# Transceivers_Ver2.net
KiCad netlist of a schematic drawn in EAGLE
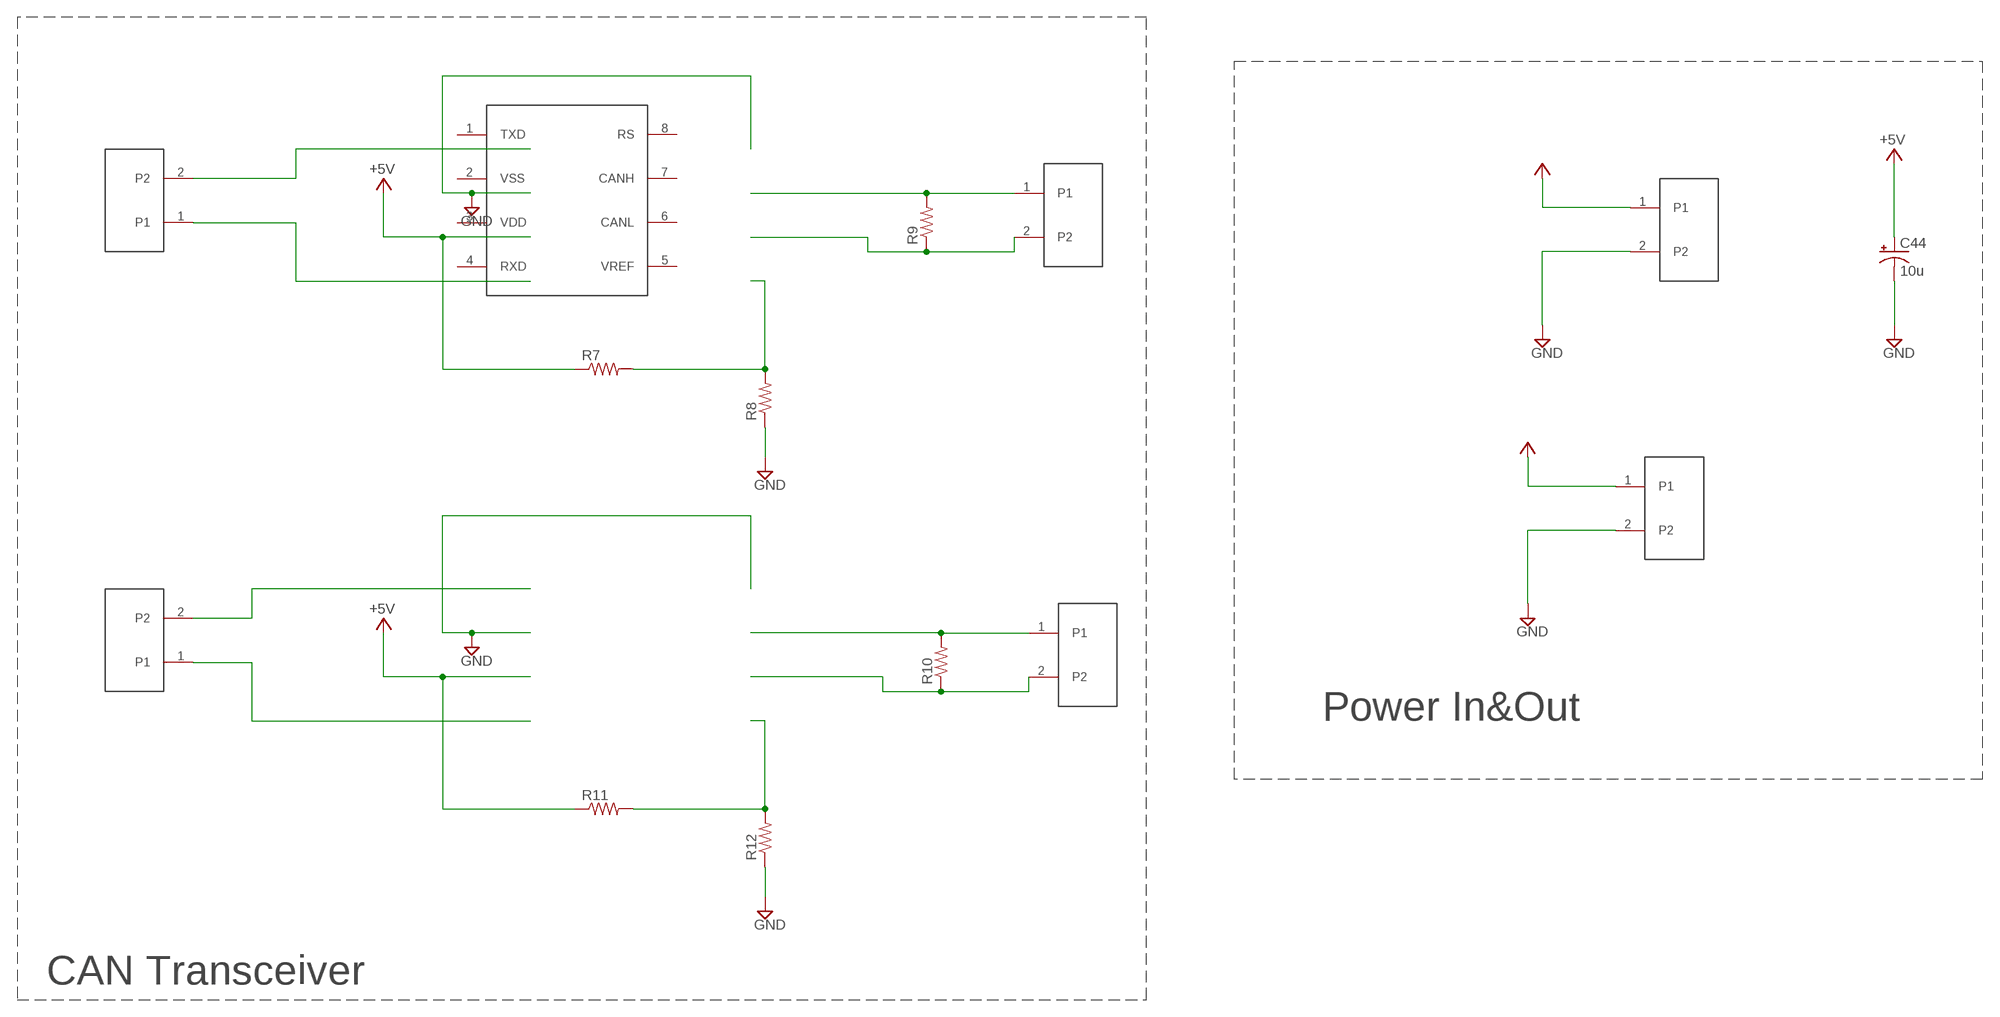
[diagram p0: schematic, sheet 1]

(export (version "E")
  (design (tool "Eeschema 10.0.6"))
  (components
    (comp (ref "C44")
      (value "10u")
      (footprint "eagle-import:153CLV-0405")
      (libsource (lib "eagle-import") (part "CPOL-US153CLV-0405"))
    )
    (comp (ref "CAN0")
      (value "CON-100MIL")
      (footprint "eagle-import:2X1-100MIL")
      (libsource (lib "eagle-import") (part "CON-100MIL"))
    )
    (comp (ref "CAN1")
      (value "CON-100MIL")
      (footprint "eagle-import:2X1-100MIL")
      (libsource (lib "eagle-import") (part "CON-100MIL"))
    )
    (comp (ref "POWER")
      (value "CON-100MIL")
      (footprint "eagle-import:2X1-100MIL")
      (libsource (lib "eagle-import") (part "CON-100MIL"))
    )
    (comp (ref "POWER1")
      (value "CON-100MIL")
      (footprint "eagle-import:2X1-100MIL")
      (libsource (lib "eagle-import") (part "CON-100MIL"))
    )
    (comp (ref "R7")
      (value "R-US_R0805")
      (footprint "eagle-import:R0805")
      (libsource (lib "eagle-import") (part "R-US_R0805"))
    )
    (comp (ref "R8")
      (value "R-US_R0805")
      (footprint "eagle-import:R0805")
      (libsource (lib "eagle-import") (part "R-US_R0805"))
    )
    (comp (ref "R9")
      (value "R-US_R0805")
      (footprint "eagle-import:R0805")
      (libsource (lib "eagle-import") (part "R-US_R0805"))
    )
    (comp (ref "R10")
      (value "R-US_R0805")
      (footprint "eagle-import:R0805")
      (libsource (lib "eagle-import") (part "R-US_R0805"))
    )
    (comp (ref "R11")
      (value "R-US_R0805")
      (footprint "eagle-import:R0805")
      (libsource (lib "eagle-import") (part "R-US_R0805"))
    )
    (comp (ref "R12")
      (value "R-US_R0805")
      (footprint "eagle-import:R0805")
      (libsource (lib "eagle-import") (part "R-US_R0805"))
    )
    (comp (ref "TXRX0")
      (value "CON-100MIL")
      (footprint "eagle-import:2X1-100MIL")
      (libsource (lib "eagle-import") (part "CON-100MIL"))
    )
    (comp (ref "TXRX1")
      (value "CON-100MIL")
      (footprint "eagle-import:2X1-100MIL")
      (libsource (lib "eagle-import") (part "CON-100MIL"))
    )
    (comp (ref "U$1")
      (value "MCP2551-DIP")
      (footprint "eagle-import:DIL08")
      (libsource (lib "eagle-import") (part "MCP2551-DIP"))
    )
  )
  (nets
    (net (code "1") (name "+5V") (class "Default")
      (node (ref "C44") (pin "+") (pinfunction "+_+") (pintype "passive"))
      (node (ref "POWER") (pin "1") (pinfunction "P1_1") (pintype "bidirectional"))
      (node (ref "POWER1") (pin "1") (pinfunction "P1_1") (pintype "bidirectional"))
      (node (ref "R11") (pin "1") (pinfunction "1_1") (pintype "passive"))
      (node (ref "R7") (pin "1") (pinfunction "1_1") (pintype "passive"))
    )
    (net (code "2") (name "GND") (class "Default")
      (node (ref "C44") (pin "-") (pinfunction "-_-") (pintype "passive"))
      (node (ref "POWER") (pin "2") (pinfunction "P2_2") (pintype "bidirectional"))
      (node (ref "POWER1") (pin "2") (pinfunction "P2_2") (pintype "bidirectional"))
      (node (ref "R12") (pin "1") (pinfunction "1_1") (pintype "passive"))
      (node (ref "R8") (pin "1") (pinfunction "1_1") (pintype "passive"))
    )
    (net (code "3") (name "Net-(CAN0-P1)") (class "Default")
      (node (ref "CAN0") (pin "1") (pinfunction "P1_1") (pintype "bidirectional"))
      (node (ref "R9") (pin "2") (pinfunction "2_2") (pintype "passive"))
    )
    (net (code "4") (name "Net-(CAN0-P2)") (class "Default")
      (node (ref "CAN0") (pin "2") (pinfunction "P2_2") (pintype "bidirectional"))
      (node (ref "R9") (pin "1") (pinfunction "1_1") (pintype "passive"))
    )
    (net (code "5") (name "Net-(CAN1-P1)") (class "Default")
      (node (ref "CAN1") (pin "1") (pinfunction "P1_1") (pintype "bidirectional"))
      (node (ref "R10") (pin "2") (pinfunction "2_2") (pintype "passive"))
    )
    (net (code "6") (name "Net-(CAN1-P2)") (class "Default")
      (node (ref "CAN1") (pin "2") (pinfunction "P2_2") (pintype "bidirectional"))
      (node (ref "R10") (pin "1") (pinfunction "1_1") (pintype "passive"))
    )
    (net (code "7") (name "Net-(R7-Pad2)") (class "Default")
      (node (ref "R7") (pin "2") (pinfunction "2_2") (pintype "passive"))
      (node (ref "R8") (pin "2") (pinfunction "2_2") (pintype "passive"))
    )
    (net (code "8") (name "Net-(R11-Pad2)") (class "Default")
      (node (ref "R11") (pin "2") (pinfunction "2_2") (pintype "passive"))
      (node (ref "R12") (pin "2") (pinfunction "2_2") (pintype "passive"))
    )
    (net (code "9") (name "unconnected-(TXRX0-P1-Pad1)") (class "Default")
      (node (ref "TXRX0") (pin "1") (pinfunction "P1_1") (pintype "bidirectional"))
    )
    (net (code "10") (name "unconnected-(TXRX0-P2-Pad2)") (class "Default")
      (node (ref "TXRX0") (pin "2") (pinfunction "P2_2") (pintype "bidirectional"))
    )
    (net (code "11") (name "unconnected-(TXRX1-P1-Pad1)") (class "Default")
      (node (ref "TXRX1") (pin "1") (pinfunction "P1_1") (pintype "bidirectional"))
    )
    (net (code "12") (name "unconnected-(TXRX1-P2-Pad2)") (class "Default")
      (node (ref "TXRX1") (pin "2") (pinfunction "P2_2") (pintype "bidirectional"))
    )
    (net (code "13") (name "unconnected-(U$1-CANH-Pad7)") (class "Default")
      (node (ref "U$1") (pin "7") (pinfunction "CANH_7") (pintype "bidirectional"))
    )
    (net (code "14") (name "unconnected-(U$1-CANL-Pad6)") (class "Default")
      (node (ref "U$1") (pin "6") (pinfunction "CANL_6") (pintype "bidirectional"))
    )
    (net (code "15") (name "unconnected-(U$1-RS-Pad8)") (class "Default")
      (node (ref "U$1") (pin "8") (pinfunction "RS_8") (pintype "bidirectional"))
    )
    (net (code "16") (name "unconnected-(U$1-RXD-Pad4)") (class "Default")
      (node (ref "U$1") (pin "4") (pinfunction "RXD_4") (pintype "bidirectional"))
    )
    (net (code "17") (name "unconnected-(U$1-TXD-Pad1)") (class "Default")
      (node (ref "U$1") (pin "1") (pinfunction "TXD_1") (pintype "bidirectional"))
    )
    (net (code "18") (name "unconnected-(U$1-VDD-Pad3)") (class "Default")
      (node (ref "U$1") (pin "3") (pinfunction "VDD_3") (pintype "bidirectional"))
    )
    (net (code "19") (name "unconnected-(U$1-VREF-Pad5)") (class "Default")
      (node (ref "U$1") (pin "5") (pinfunction "VREF_5") (pintype "bidirectional"))
    )
    (net (code "20") (name "unconnected-(U$1-VSS-Pad2)") (class "Default")
      (node (ref "U$1") (pin "2") (pinfunction "VSS_2") (pintype "bidirectional"))
    )
  )
)
